# IO_Peripherals.net
KiCad netlist of a schematic drawn in Altium Designer
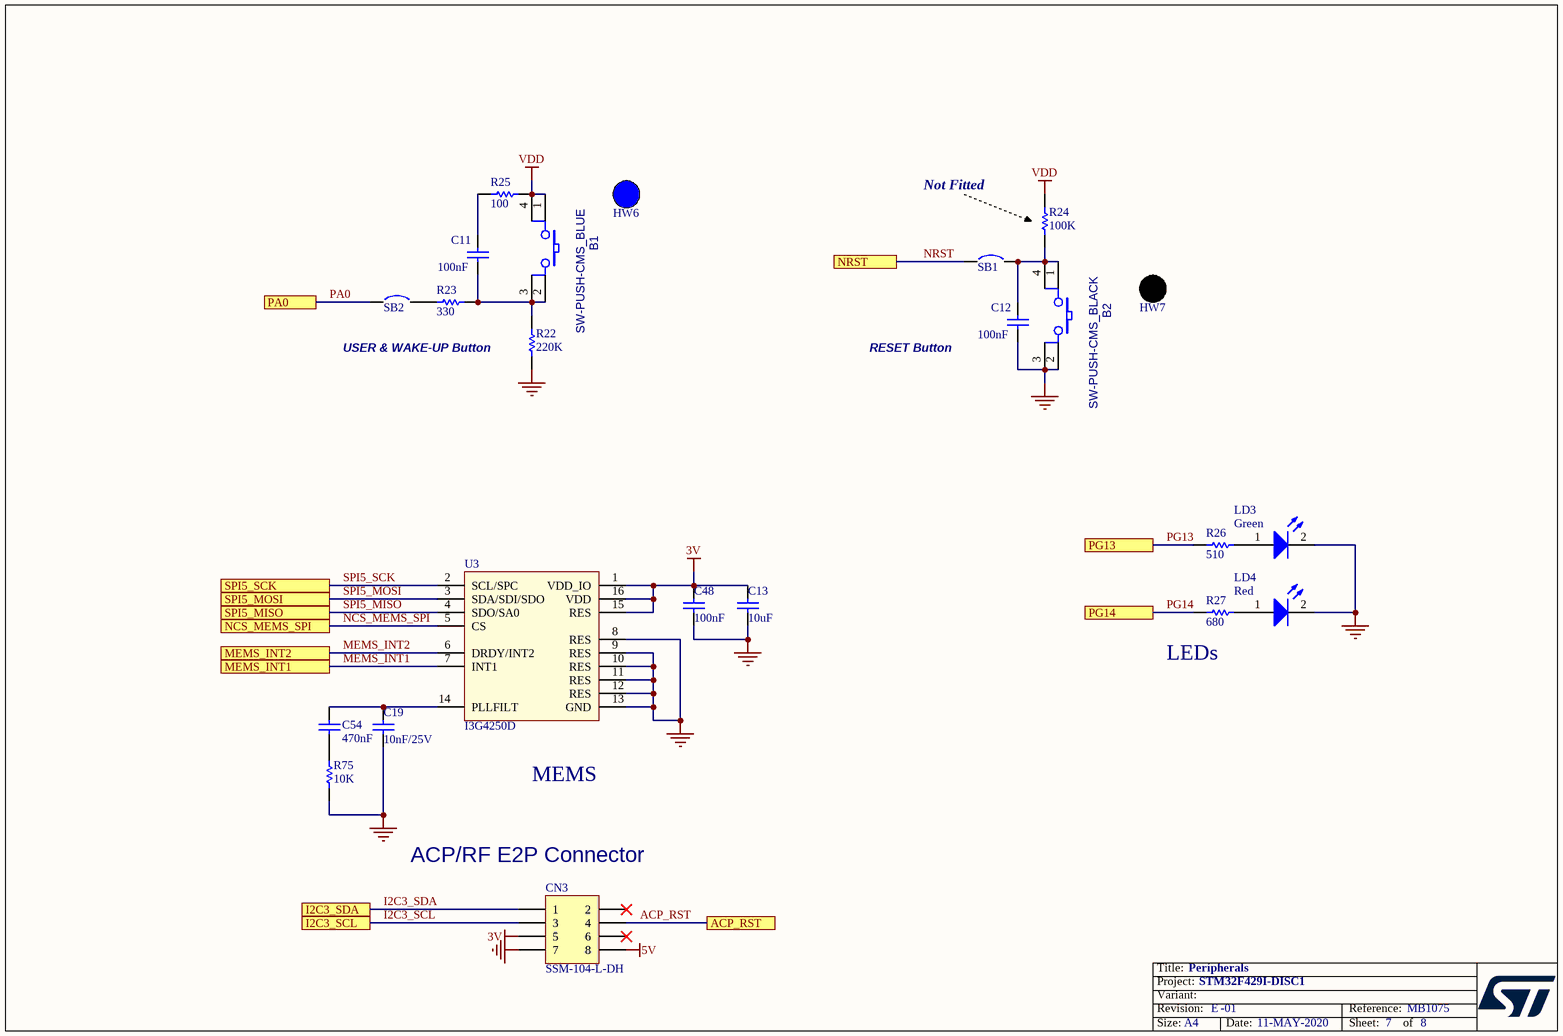
[diagram p0: IO_Peripherals.SchDoc]

(export (version "E")
  (design (tool "Eeschema 10.0.6"))
  (components
    (comp (ref "B1")
      (value "SW-PUSH-CMS_BLUE")
      (footprint "BP1CMS")
      (description "Non-Open Push-Button 0.1A 24V")
      (libsource (lib "MCD_TOOLS") (part "SW-PUSH-CMS_BLUE"))
    )
    (comp (ref "B2")
      (value "SW-PUSH-CMS_BLACK")
      (footprint "BP1CMS")
      (description "Non-Open Push-Button 0.1A 24V")
      (libsource (lib "MCD_TOOLS") (part "SW-PUSH-CMS_BLACK"))
    )
    (comp (ref "C11")
      (value "100nF")
      (footprint "0402C")
      (description "Capacitor 0402 / 0603 / 0805")
      (libsource (lib "MCD_TOOLS") (part "Capacitor_ST"))
    )
    (comp (ref "C12")
      (value "100nF")
      (footprint "0402C")
      (description "Capacitor 0402 / 0603 / 0805")
      (libsource (lib "MCD_TOOLS") (part "Capacitor_ST"))
    )
    (comp (ref "C13")
      (value "10uF")
      (footprint "0603C")
      (description "Capacitor")
      (fields (field (name "PUBLISHER") "Altium Limited"))
      (libsource (lib "Miscellaneous Devices") (part "CAP"))
    )
    (comp (ref "C19")
      (value "10nF/25V")
      (footprint "0603C")
      (description "Capacitor")
      (fields (field (name "PUBLISHER") "Altium Limited"))
      (libsource (lib "Miscellaneous Devices") (part "CAP"))
    )
    (comp (ref "C48")
      (value "100nF")
      (footprint "0402C")
      (description "Capacitor 0402 / 0603 / 0805")
      (libsource (lib "MCD_TOOLS") (part "Capacitor_ST"))
    )
    (comp (ref "C54")
      (value "470nF")
      (footprint "C0603")
      (description "Capacitor, MLCC, 470nF, 16V, X7R, 10%, 0603, T=0.8mm")
      (fields
        (field (name "INTERNAL_PART_NUMBER") "MCD-01006")
        (field (name "MANUFACTURER_PART_NUMBER") "CC0603KRX7R7BB474")
        (field (name "PROVIDED_BY") "SUBCO")
      )
      (libsource (lib "MCD_PARTS_database") (part "Capacitor"))
    )
    (comp (ref "CN3")
      (value "SSM-104-L-DH")
      (footprint "SSM-104-L-DH")
      (description "Header, 5-Pin, Dual row")
      (fields (field (name "PUBLISHER") "Altium Limited"))
      (libsource (lib "mb1045") (part "SSM-104-L-DH"))
    )
    (comp (ref "HW6") (value "BUTTON_HAT_BLUE") (libsource (lib "MB1075") (part "BUTTON_HAT_BLUE")))
    (comp (ref "HW7") (value "BUTTON_HAT_BLACK") (libsource (lib "MB1075") (part "BUTTON_HAT_BLACK")))
    (comp (ref "LD3")
      (value "Green")
      (footprint "0603D")
      (description "Typical RED, GREEN, YELLOW, AMBER GaAs LED")
      (fields (field (name "PUBLISHER") "Altium Limited"))
      (libsource (lib "Miscellaneous Devices") (part "LED2"))
    )
    (comp (ref "LD4")
      (value "Red")
      (footprint "0603D")
      (description "Typical RED, GREEN, YELLOW, AMBER GaAs LED")
      (fields (field (name "PUBLISHER") "Altium Limited"))
      (libsource (lib "Miscellaneous Devices") (part "LED2"))
    )
    (comp (ref "R22")
      (value "220K")
      (footprint "0402R")
      (description "Resistor 0402 / 0603 / 0805")
      (libsource (lib "MCD_TOOLS") (part "Resistor_ST"))
    )
    (comp (ref "R23")
      (value "330")
      (footprint "0402R")
      (description "Resistor 0402 / 0603 / 0805")
      (libsource (lib "MCD_TOOLS") (part "Resistor_ST"))
    )
    (comp (ref "R24")
      (value "100K")
      (footprint "0402R")
      (description "Resistor 0402 / 0603 / 0805")
      (libsource (lib "MCD_TOOLS") (part "Resistor_ST"))
    )
    (comp (ref "R25")
      (value "100")
      (footprint "0402R")
      (description "Resistor 0402 / 0603 / 0805")
      (libsource (lib "MCD_TOOLS") (part "Resistor_ST"))
    )
    (comp (ref "R26")
      (value "510")
      (footprint "0603R")
      (description "Resistor 0402 / 0603 / 0805")
      (libsource (lib "MCD_TOOLS") (part "Resistor_ST"))
    )
    (comp (ref "R27")
      (value "680")
      (footprint "0603R")
      (description "Resistor 0402 / 0603 / 0805")
      (libsource (lib "MCD_TOOLS") (part "Resistor_ST"))
    )
    (comp (ref "R75")
      (value "10K")
      (footprint "0402R")
      (description "Resistor 0402 / 0603 / 0805")
      (libsource (lib "MCD_TOOLS") (part "Resistor_ST"))
    )
    (comp (ref "SB1")
      (value "Circuit Breaker")
      (footprint "JP2_SMD")
      (fields (field (name "PUBLISHER") "Altium Limited"))
      (libsource (lib "MB915") (part "Circuit Breaker"))
    )
    (comp (ref "SB2")
      (value "Circuit Breaker")
      (footprint "JP2_SMD")
      (fields (field (name "PUBLISHER") "Altium Limited"))
      (libsource (lib "MB915") (part "Circuit Breaker"))
    )
    (comp (ref "U3")
      (value "I3G4250D")
      (footprint "ICC_LGA16_4X4_P065_H1P1")
      (description "MEMS motion sensor: 3-axis digital output gyroscope LG4-16 4x4mm")
      (fields
        (field (name "INTERNAL_PART_NUMBER") "MCD-01963")
        (field (name "MANUFACTURER") "STMICROELECTRONICS")
        (field (name "PROVIDED_BY") "SUBCO with ST control")
      )
      (libsource (lib "MCD_PARTS_database") (part "I3G4250D"))
    )
  )
  (nets
    (net (code "1") (name "/ACP_RST") (class "Default")
      (node (ref "CN3") (pin "4") (pinfunction "4_4") (pintype "passive"))
    )
    (net (code "2") (name "/I2C3_SCL") (class "Default")
      (node (ref "CN3") (pin "3") (pinfunction "3_3") (pintype "passive"))
    )
    (net (code "3") (name "/I2C3_SDA") (class "Default")
      (node (ref "CN3") (pin "1") (pinfunction "1_1") (pintype "passive"))
    )
    (net (code "4") (name "/MEMS_INT1") (class "Default")
      (node (ref "U3") (pin "7") (pinfunction "INT1_7") (pintype "passive"))
    )
    (net (code "5") (name "/MEMS_INT2") (class "Default")
      (node (ref "U3") (pin "6") (pinfunction "DRDY/INT2_6") (pintype "passive"))
    )
    (net (code "6") (name "/NCS_MEMS_SPI") (class "Default")
      (node (ref "U3") (pin "5") (pinfunction "CS_5") (pintype "passive"))
    )
    (net (code "7") (name "/NRST") (class "Default")
      (node (ref "SB1") (pin "1") (pinfunction "1_1") (pintype "passive"))
    )
    (net (code "8") (name "/PA0") (class "Default")
      (node (ref "SB2") (pin "1") (pinfunction "1_1") (pintype "passive"))
    )
    (net (code "9") (name "/PG13") (class "Default")
      (node (ref "R26") (pin "1") (pinfunction "1_1") (pintype "passive"))
    )
    (net (code "10") (name "/PG14") (class "Default")
      (node (ref "R27") (pin "1") (pinfunction "1_1") (pintype "passive"))
    )
    (net (code "11") (name "/SPI5_MISO") (class "Default")
      (node (ref "U3") (pin "4") (pinfunction "SDO/SA0_4") (pintype "passive"))
    )
    (net (code "12") (name "/SPI5_MOSI") (class "Default")
      (node (ref "U3") (pin "3") (pinfunction "SDA/SDI/SDO_3") (pintype "passive"))
    )
    (net (code "13") (name "/SPI5_SCK") (class "Default")
      (node (ref "U3") (pin "2") (pinfunction "SCL/SPC_2") (pintype "passive"))
    )
    (net (code "14") (name "3V") (class "Default")
      (node (ref "C13") (pin "2") (pinfunction "2_2") (pintype "passive"))
      (node (ref "C48") (pin "2") (pinfunction "2_2") (pintype "passive"))
      (node (ref "CN3") (pin "5") (pinfunction "5_5") (pintype "passive"))
      (node (ref "U3") (pin "1") (pinfunction "VDD_IO_1") (pintype "passive"))
      (node (ref "U3") (pin "15") (pinfunction "RES_15") (pintype "passive"))
      (node (ref "U3") (pin "16") (pinfunction "VDD_16") (pintype "passive"))
    )
    (net (code "15") (name "5V") (class "Default")
      (node (ref "CN3") (pin "8") (pinfunction "8_8") (pintype "passive"))
    )
    (net (code "16") (name "GND") (class "Default")
      (node (ref "B2") (pin "2") (pinfunction "2_2") (pintype "passive"))
      (node (ref "B2") (pin "3") (pinfunction "3_3") (pintype "passive"))
      (node (ref "C12") (pin "1") (pinfunction "1_1") (pintype "passive"))
      (node (ref "C13") (pin "1") (pinfunction "1_1") (pintype "passive"))
      (node (ref "C19") (pin "1") (pinfunction "1_1") (pintype "passive"))
      (node (ref "C48") (pin "1") (pinfunction "1_1") (pintype "passive"))
      (node (ref "CN3") (pin "7") (pinfunction "7_7") (pintype "passive"))
      (node (ref "LD3") (pin "2") (pinfunction "K_2") (pintype "passive"))
      (node (ref "LD4") (pin "2") (pinfunction "K_2") (pintype "passive"))
      (node (ref "R22") (pin "1") (pinfunction "1_1") (pintype "passive"))
      (node (ref "R75") (pin "1") (pinfunction "1_1") (pintype "passive"))
      (node (ref "U3") (pin "10") (pinfunction "RES_10") (pintype "passive"))
      (node (ref "U3") (pin "11") (pinfunction "RES_11") (pintype "passive"))
      (node (ref "U3") (pin "12") (pinfunction "RES_12") (pintype "passive"))
      (node (ref "U3") (pin "13") (pinfunction "GND_13") (pintype "passive"))
      (node (ref "U3") (pin "8") (pinfunction "RES_8") (pintype "passive"))
      (node (ref "U3") (pin "9") (pinfunction "RES_9") (pintype "passive"))
    )
    (net (code "17") (name "Net-(B1-Pad2)") (class "Default")
      (node (ref "B1") (pin "2") (pinfunction "2_2") (pintype "passive"))
      (node (ref "B1") (pin "3") (pinfunction "3_3") (pintype "passive"))
      (node (ref "C11") (pin "1") (pinfunction "1_1") (pintype "passive"))
      (node (ref "R22") (pin "2") (pinfunction "2_2") (pintype "passive"))
      (node (ref "R23") (pin "2") (pinfunction "2_2") (pintype "passive"))
    )
    (net (code "18") (name "Net-(B2-Pad1)") (class "Default")
      (node (ref "B2") (pin "1") (pinfunction "1_1") (pintype "passive"))
      (node (ref "B2") (pin "4") (pinfunction "4_4") (pintype "passive"))
      (node (ref "C12") (pin "2") (pinfunction "2_2") (pintype "passive"))
      (node (ref "R24") (pin "1") (pinfunction "1_1") (pintype "passive"))
      (node (ref "SB1") (pin "2") (pinfunction "2_2") (pintype "passive"))
    )
    (net (code "19") (name "Net-(C11-Pad2)") (class "Default")
      (node (ref "C11") (pin "2") (pinfunction "2_2") (pintype "passive"))
      (node (ref "R25") (pin "1") (pinfunction "1_1") (pintype "passive"))
    )
    (net (code "20") (name "Net-(C54-Pad1)") (class "Default")
      (node (ref "C54") (pin "1") (pinfunction "1_1") (pintype "passive"))
      (node (ref "R75") (pin "2") (pinfunction "2_2") (pintype "passive"))
    )
    (net (code "21") (name "Net-(LD3-A)") (class "Default")
      (node (ref "LD3") (pin "1") (pinfunction "A_1") (pintype "passive"))
      (node (ref "R26") (pin "2") (pinfunction "2_2") (pintype "passive"))
    )
    (net (code "22") (name "Net-(LD4-A)") (class "Default")
      (node (ref "LD4") (pin "1") (pinfunction "A_1") (pintype "passive"))
      (node (ref "R27") (pin "2") (pinfunction "2_2") (pintype "passive"))
    )
    (net (code "23") (name "Net-(R23-Pad1)") (class "Default")
      (node (ref "R23") (pin "1") (pinfunction "1_1") (pintype "passive"))
      (node (ref "SB2") (pin "2") (pinfunction "2_2") (pintype "passive"))
    )
    (net (code "24") (name "Net-(U3-PLLFILT)") (class "Default")
      (node (ref "C19") (pin "2") (pinfunction "2_2") (pintype "passive"))
      (node (ref "C54") (pin "2") (pinfunction "2_2") (pintype "passive"))
      (node (ref "U3") (pin "14") (pinfunction "PLLFILT_14") (pintype "passive"))
    )
    (net (code "25") (name "VDD") (class "Default")
      (node (ref "B1") (pin "1") (pinfunction "1_1") (pintype "passive"))
      (node (ref "B1") (pin "4") (pinfunction "4_4") (pintype "passive"))
      (node (ref "R24") (pin "2") (pinfunction "2_2") (pintype "passive"))
      (node (ref "R25") (pin "2") (pinfunction "2_2") (pintype "passive"))
    )
    (net (code "26") (name "unconnected-(CN3-Pad2)") (class "Default")
      (node (ref "CN3") (pin "2") (pinfunction "2_2") (pintype "passive+no_connect"))
    )
    (net (code "27") (name "unconnected-(CN3-Pad6)") (class "Default")
      (node (ref "CN3") (pin "6") (pinfunction "6_6") (pintype "passive+no_connect"))
    )
  )
)
